# Generic_Robot_Controller_ver1.net
KiCad netlist of a schematic drawn in EasyEDA Pro
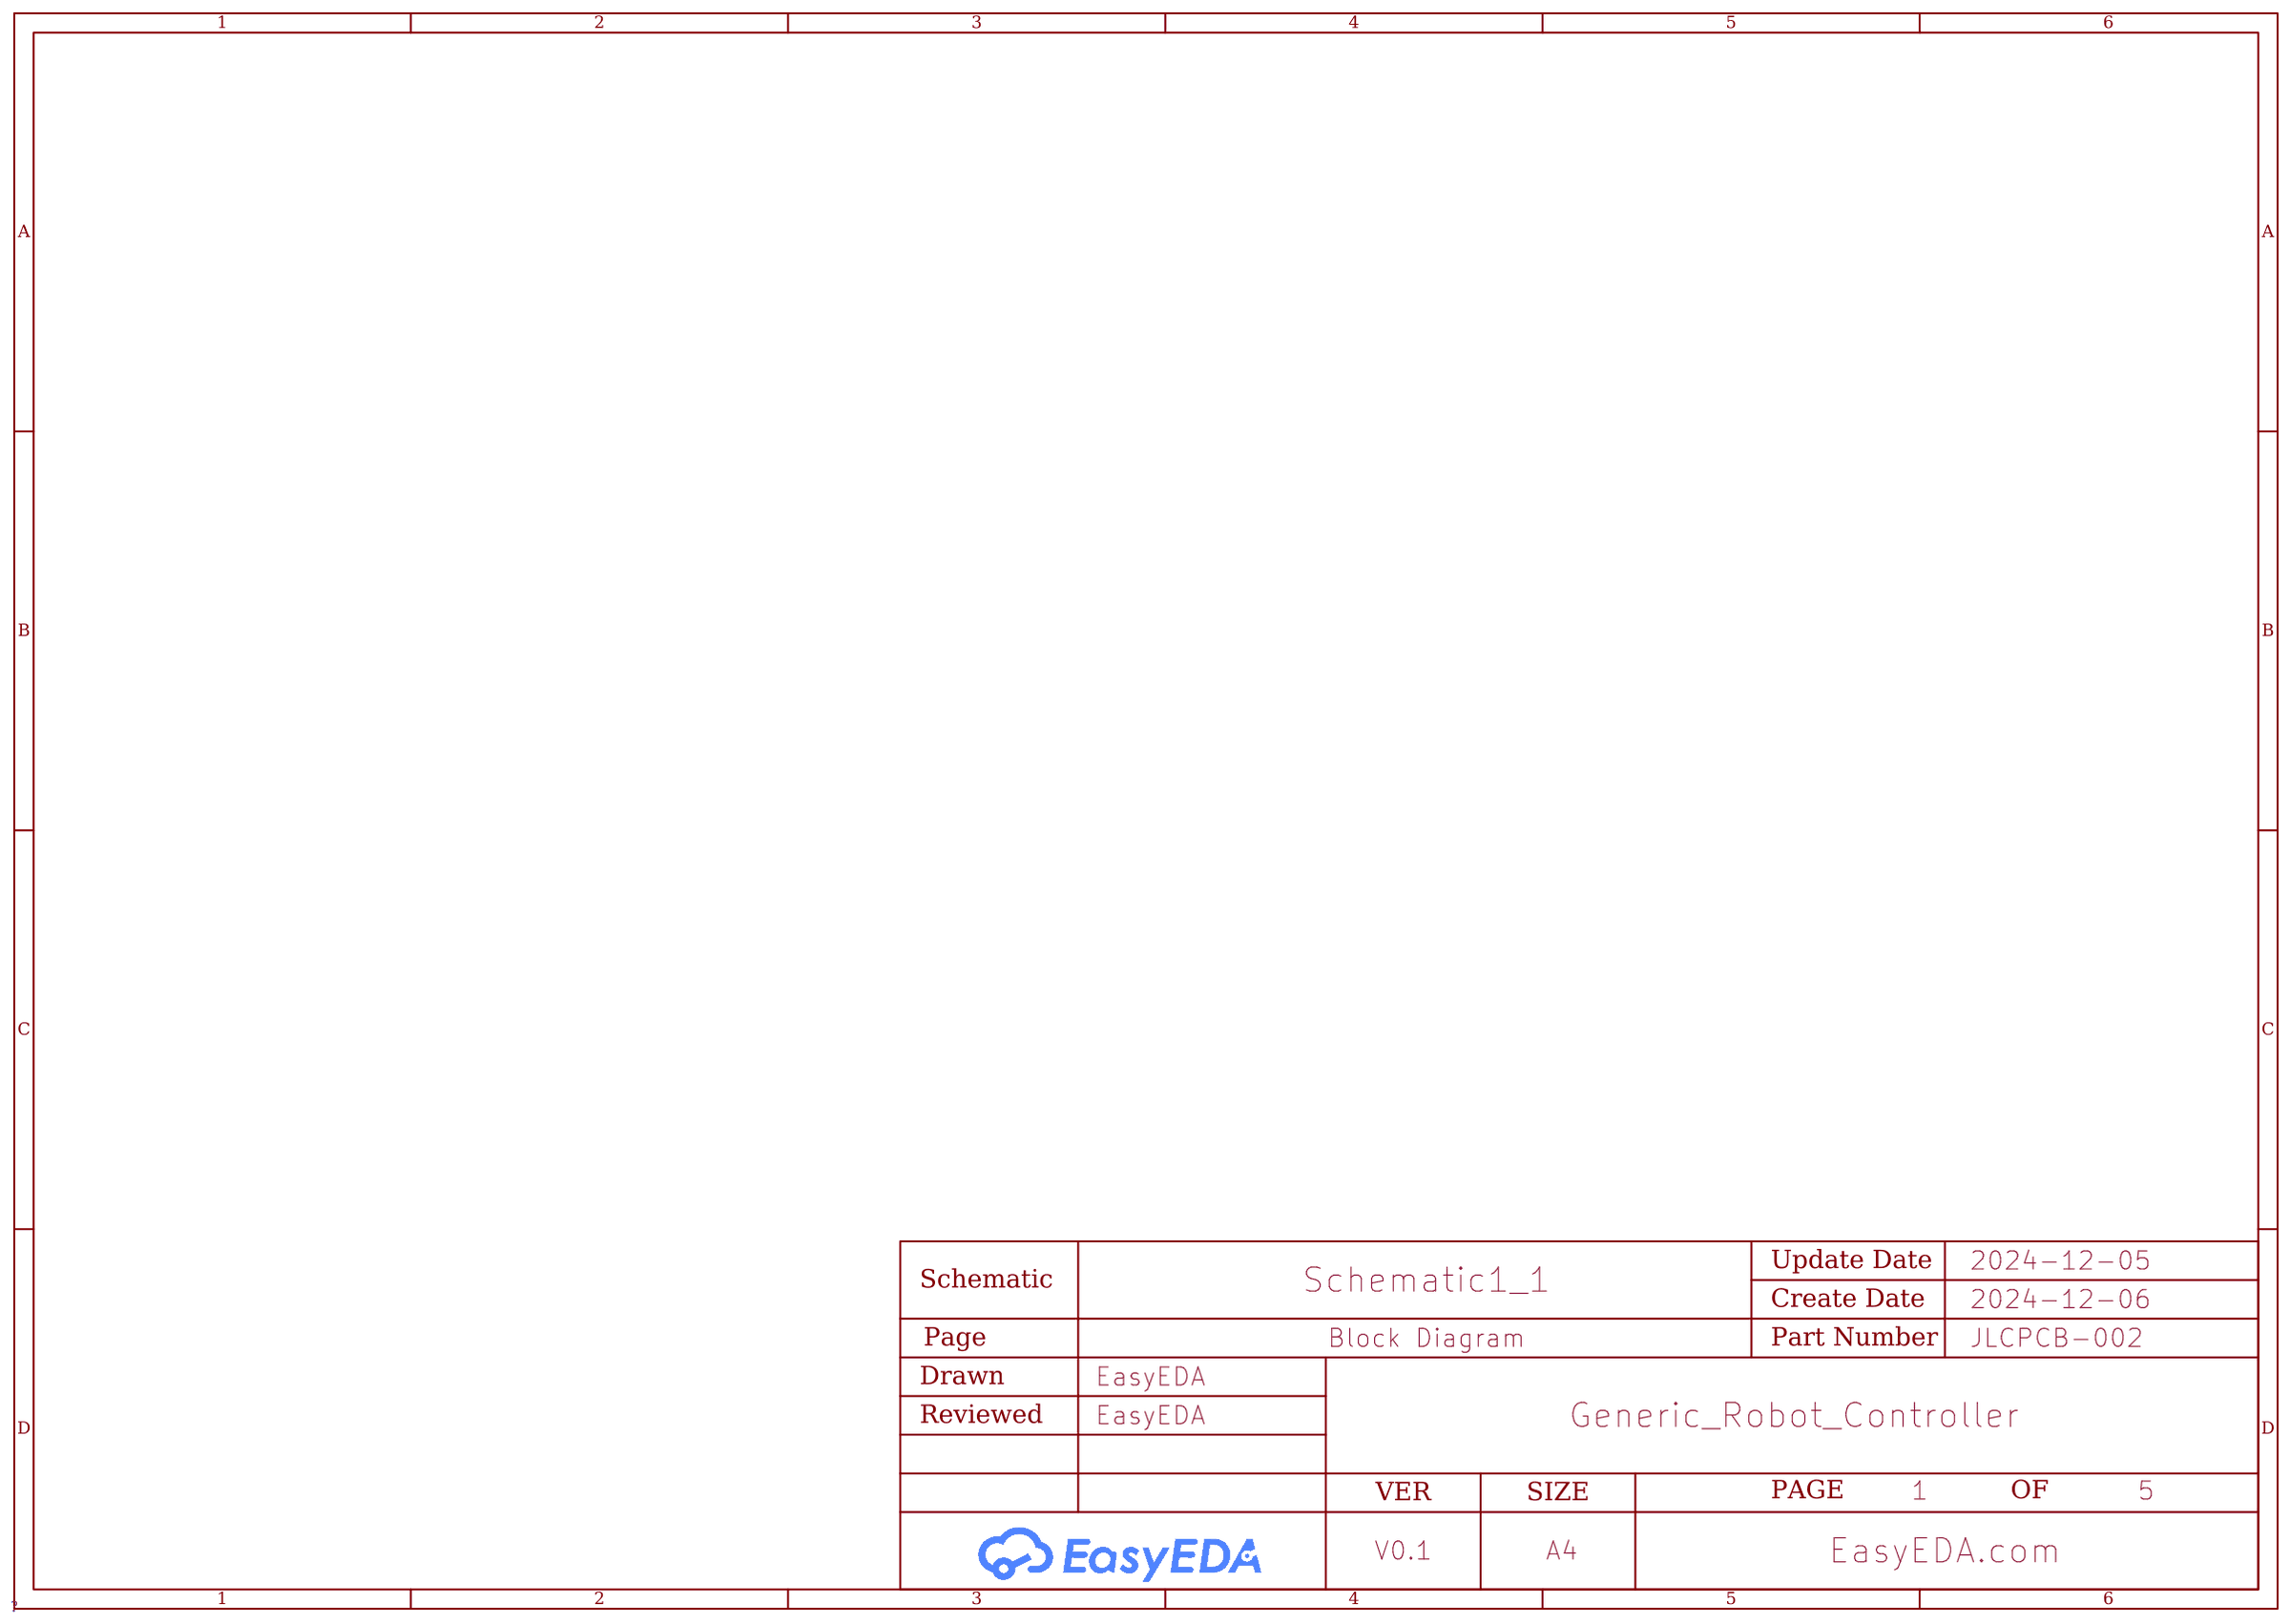
[diagram p0: Block Diagram]
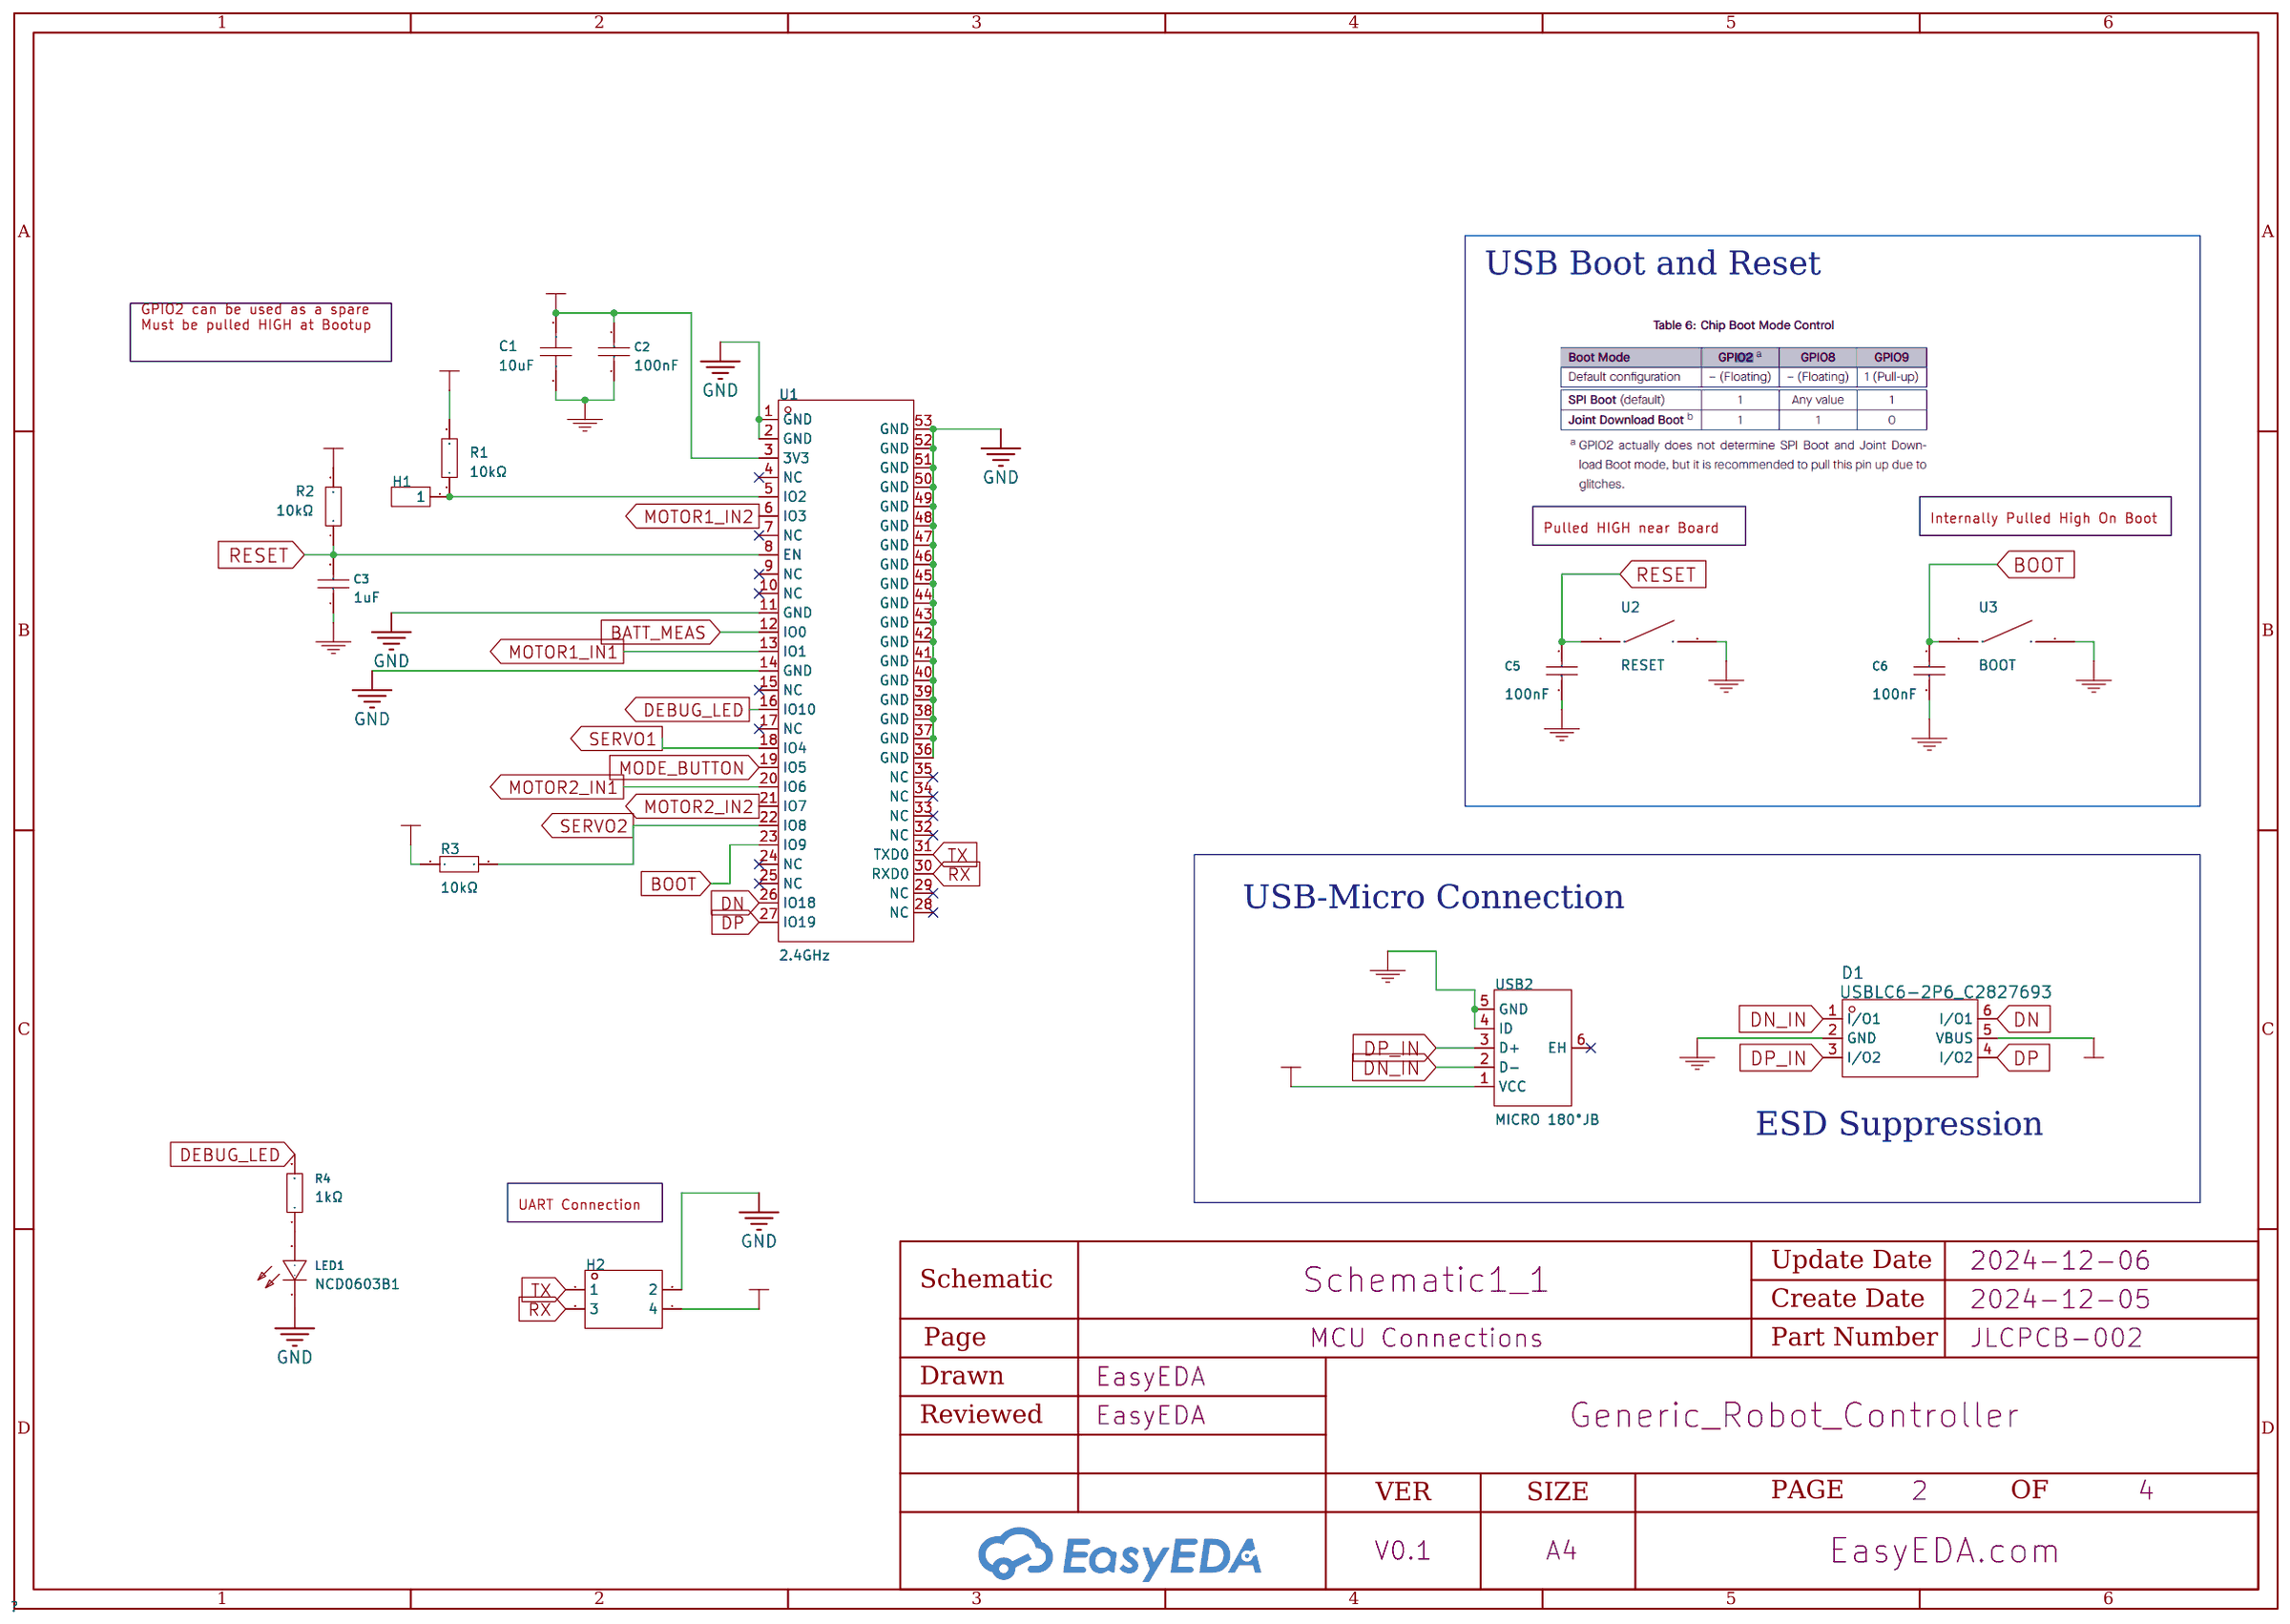
[diagram p1: MCU Connections]
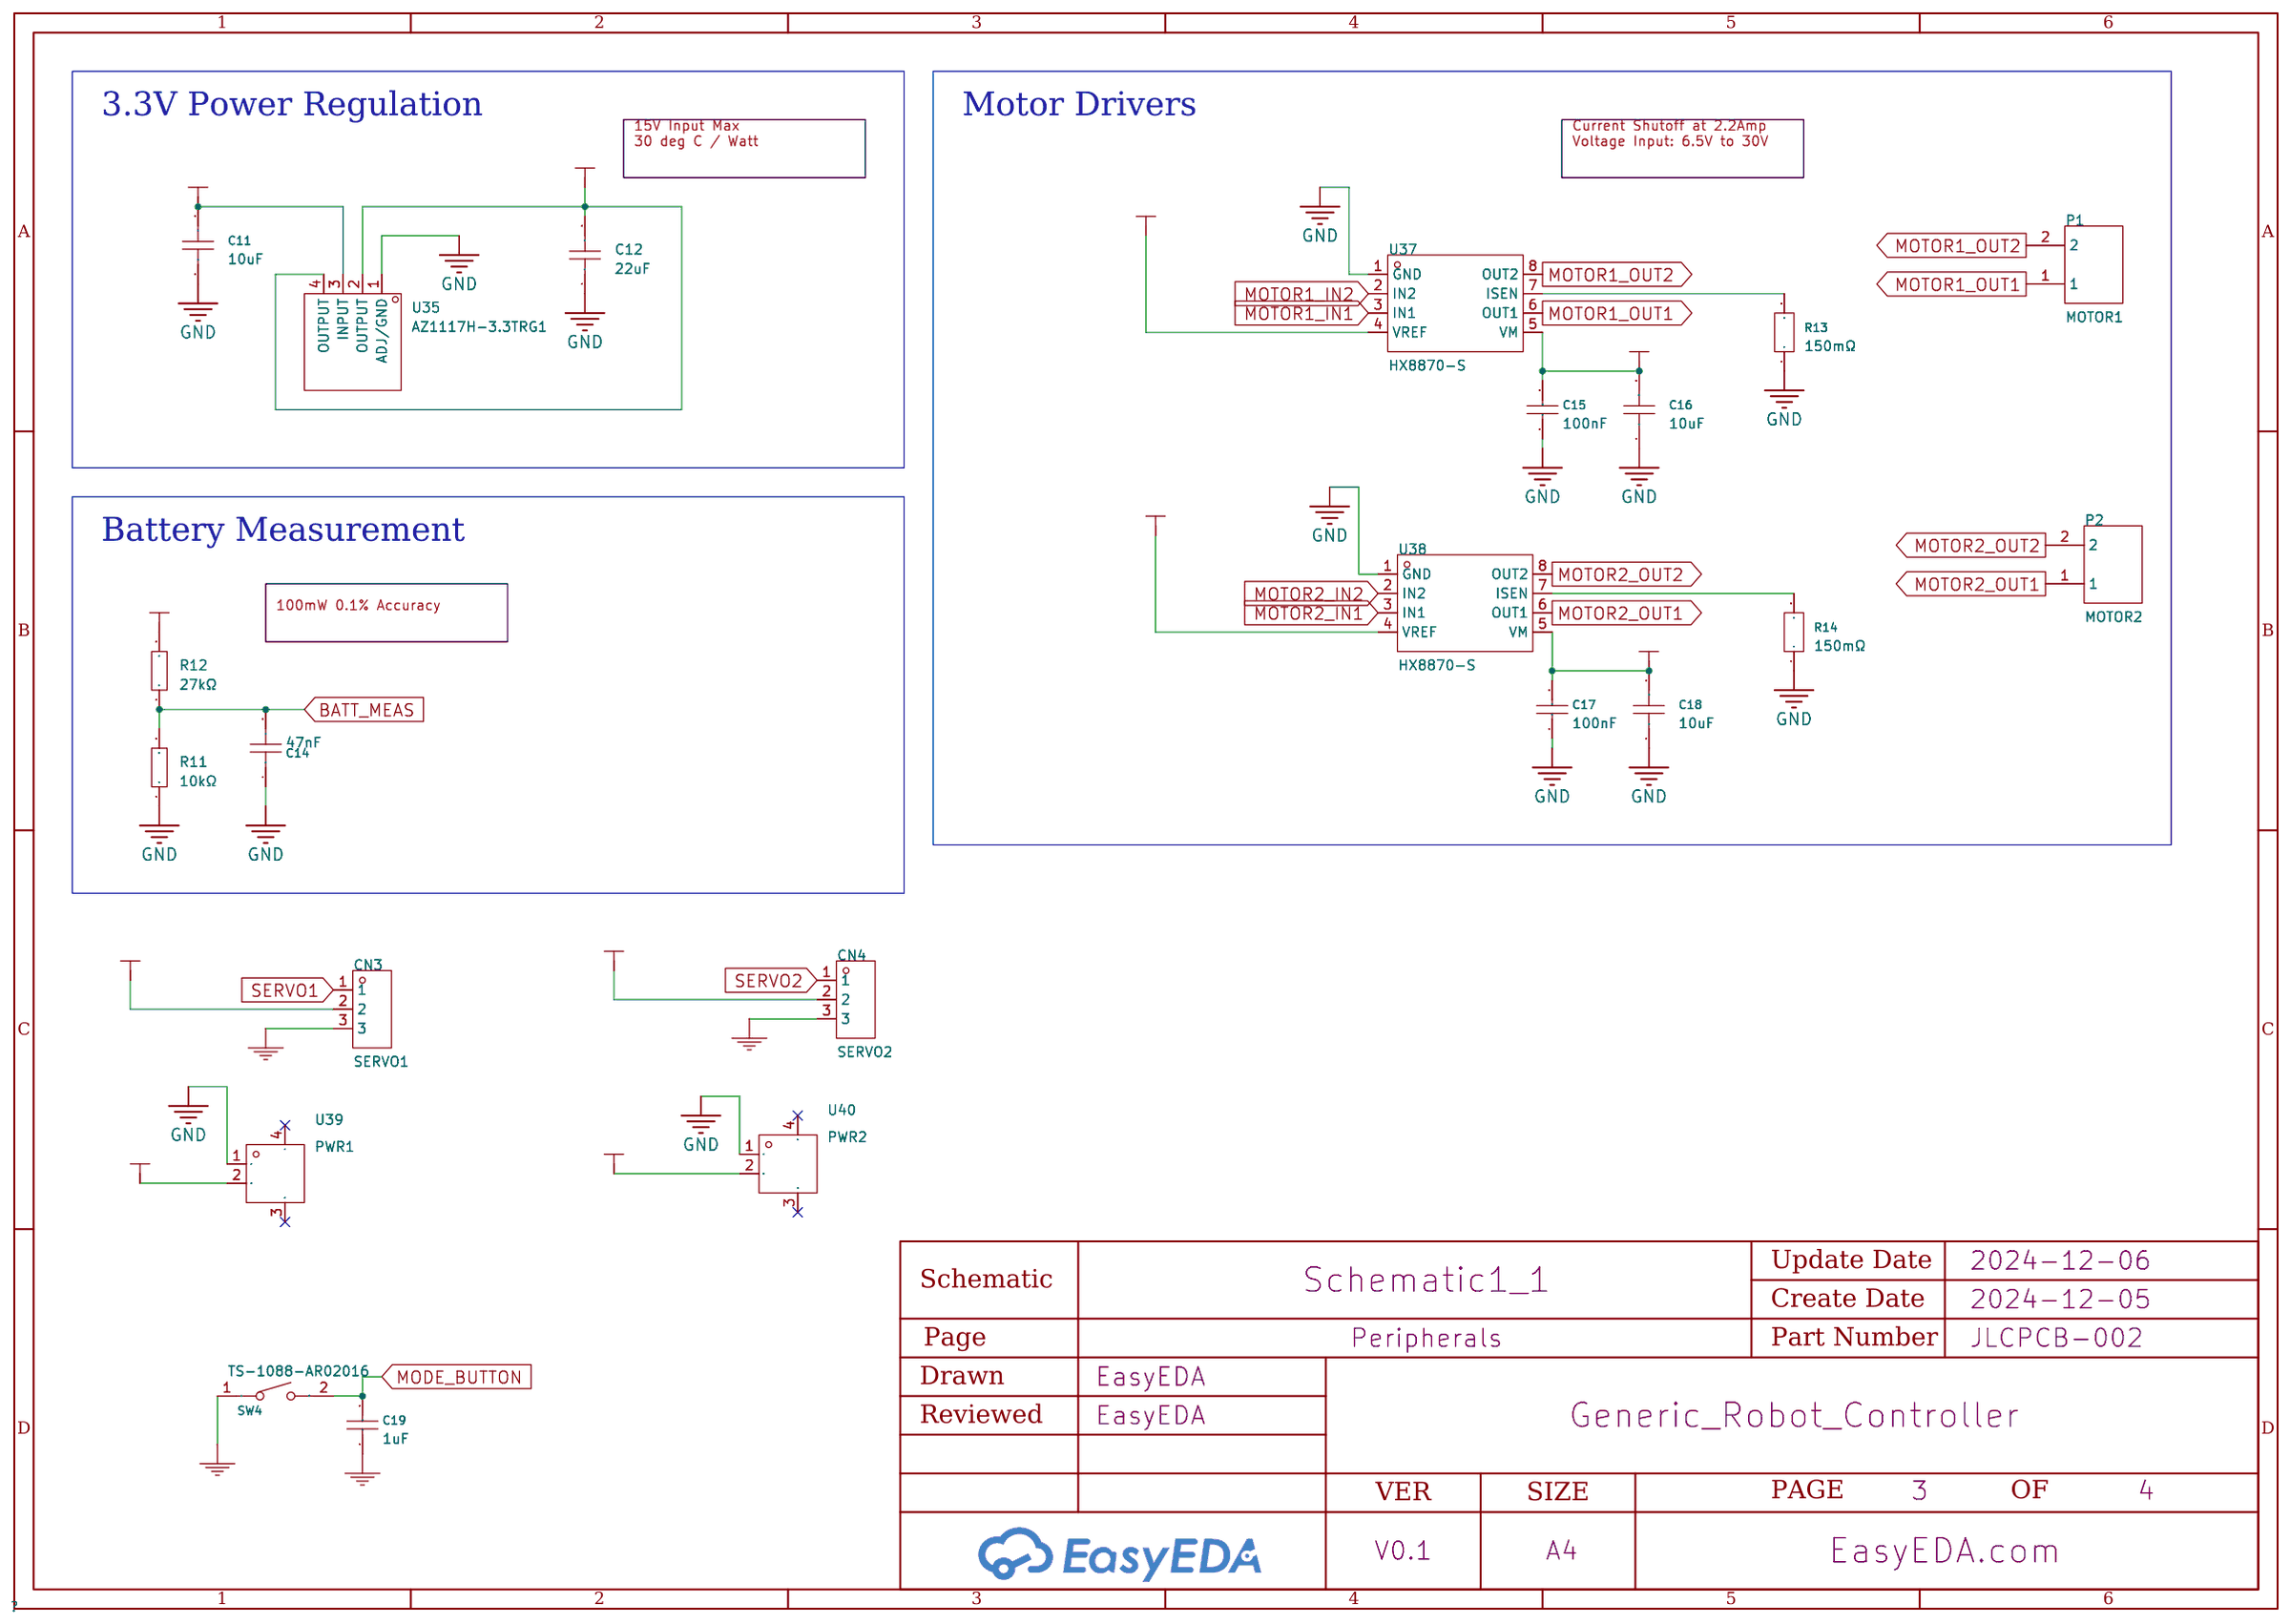
[diagram p2: Peripherals]
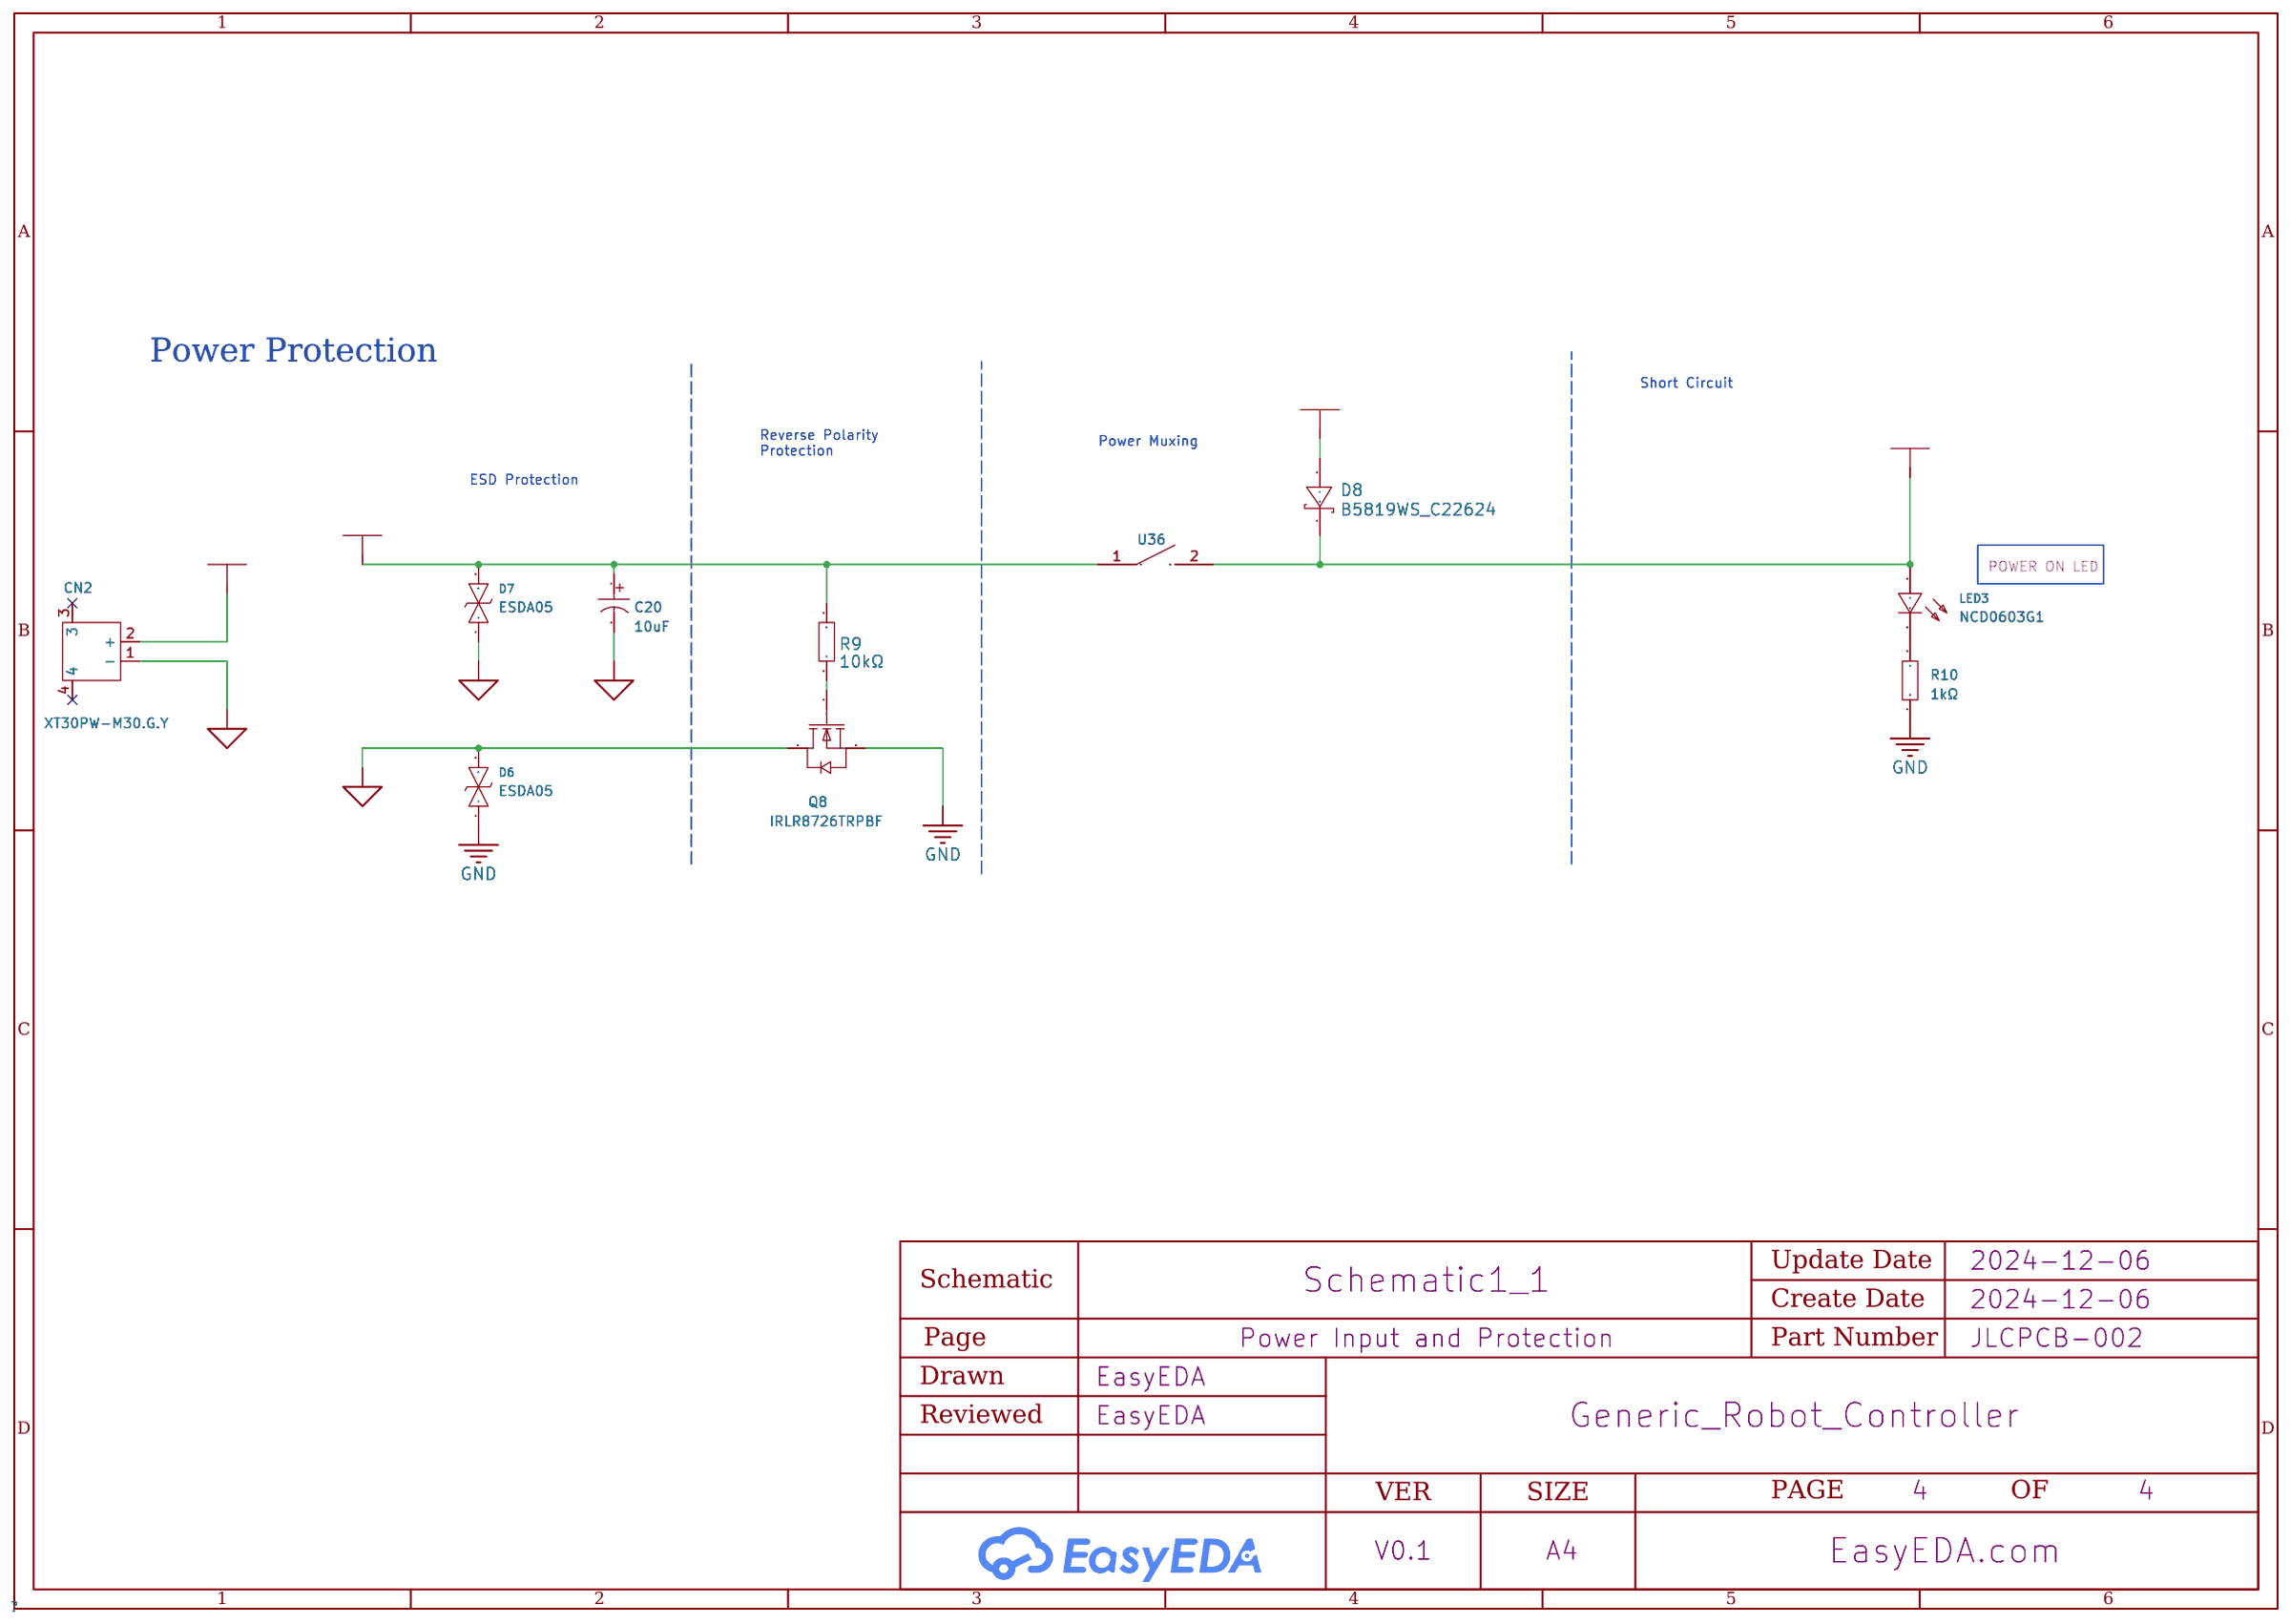
[diagram p3: Power Input and Protection]

(export (version "E")
  (design (tool "Eeschema 10.0.6"))
  (components
    (comp (ref "C1")
      (value "10uF")
      (footprint "easyedapro:C0402")
      (fields
        (field (name "Manufacturer Part") "CL05A106MP5NUNC")
        (field (name "Manufacturer") "SAMSUNG(三星)")
      )
      (libsource (lib "easyedapro") (part "CL05A106MP5NUNC_C315248"))
    )
    (comp (ref "C2")
      (value "100nF")
      (footprint "easyedapro:C0402")
      (fields
        (field (name "Manufacturer Part") "CL05B104KO5NNNC")
        (field (name "Manufacturer") "SAMSUNG(三星)")
      )
      (libsource (lib "easyedapro") (part "CL05B104KO5NNNC"))
    )
    (comp (ref "C3")
      (value "1uF")
      (footprint "easyedapro:C0402")
      (fields
        (field (name "Manufacturer Part") "CL05A105KO5NNNC")
        (field (name "Manufacturer") "SAMSUNG(三星)")
      )
      (libsource (lib "easyedapro") (part "CL05A105KO5NNNC"))
    )
    (comp (ref "C5")
      (value "100nF")
      (footprint "easyedapro:C0402")
      (fields
        (field (name "Manufacturer Part") "CL05B104KO5NNNC")
        (field (name "Manufacturer") "SAMSUNG(三星)")
      )
      (libsource (lib "easyedapro") (part "CL05B104KO5NNNC"))
    )
    (comp (ref "C6")
      (value "100nF")
      (footprint "easyedapro:C0402")
      (fields
        (field (name "Manufacturer Part") "CL05B104KO5NNNC")
        (field (name "Manufacturer") "SAMSUNG(三星)")
      )
      (libsource (lib "easyedapro") (part "CL05B104KO5NNNC"))
    )
    (comp (ref "D1")
      (value "USBLC6-2P6_C2827693")
      (footprint "easyedapro:SOT-666-6_L1.6-W1.2-P0.50-LS1.6-BL")
      (fields (field (name "Manufacturer Part") "USBLC6-2P6") (field (name "Manufacturer") "TECH PUBLIC(台舟)"))
      (libsource (lib "easyedapro") (part "USBLC6-2P6_C2827693"))
    )
    (comp (ref "H1")
      (value "~")
      (footprint "easyedapro:HDR-TH_1P-V-M_XKB_X4611WV-01I-C28D40")
      (libsource (lib "easyedapro") (part "HDR_1x1"))
    )
    (comp (ref "H2")
      (value "~")
      (footprint "easyedapro:HDR-TH_4P-P2.54-V-F-R2-C2-S2.54")
      (libsource (lib "easyedapro") (part "HDR-F-2.54_2x2"))
    )
    (comp (ref "LED1")
      (value "NCD0603B1")
      (footprint "easyedapro:LED0603-RD")
      (description "Emitted Color:blue")
      (fields (field (name "Manufacturer") "国星光电"))
      (libsource (lib "easyedapro") (part "FC-DA1608BK-470H10"))
    )
    (comp (ref "R1")
      (value "10kΩ")
      (footprint "easyedapro:R0402")
      (fields (field (name "Manufacturer Part") "RC0402FR-0710KL") (field (name "Manufacturer") "YAGEO(国巨)"))
      (libsource (lib "easyedapro") (part "RC0402FR-0710KL"))
    )
    (comp (ref "R2")
      (value "10kΩ")
      (footprint "easyedapro:R0402")
      (fields (field (name "Manufacturer Part") "RC0402FR-0710KL") (field (name "Manufacturer") "YAGEO(国巨)"))
      (libsource (lib "easyedapro") (part "RC0402FR-0710KL"))
    )
    (comp (ref "R3")
      (value "10kΩ")
      (footprint "easyedapro:R0402")
      (fields (field (name "Manufacturer Part") "RC0402FR-0710KL") (field (name "Manufacturer") "YAGEO(国巨)"))
      (libsource (lib "easyedapro") (part "RC0402FR-0710KL"))
    )
    (comp (ref "R4")
      (value "1kΩ")
      (footprint "easyedapro:R0402")
      (fields
        (field (name "Manufacturer Part") "0402WGF1001TCE")
        (field (name "Manufacturer") "UNI-ROYAL(厚声)")
      )
      (libsource (lib "easyedapro") (part "0402WGF1001TCE"))
    )
    (comp (ref "U1")
      (value "2.4GHz")
      (footprint "easyedapro:WIFIM-SMD_ESP32-C3-MINI-1")
      (fields
        (field (name "Manufacturer Part") "ESP32-C3-MINI-1-H4")
        (field (name "Manufacturer") "ESPRESSIF(乐鑫)")
      )
      (libsource (lib "easyedapro") (part "ESP32-C3-MINI-1-H4(4MB)"))
    )
    (comp (ref "U2")
      (value "RESET")
      (footprint "easyedapro:SW-SMD_4P-L3.0-W2.0-P0.85-LS3.5")
      (fields
        (field (name "Manufacturer Part") "TS2306A 240gf MSM 9")
        (field (name "Manufacturer") "SHOU HAN(首韩)")
      )
      (libsource (lib "easyedapro") (part "TS2306A 240GF MSM 9_C2976675"))
    )
    (comp (ref "U3")
      (value "BOOT")
      (footprint "easyedapro:SW-SMD_4P-L3.0-W2.0-P0.85-LS3.5")
      (fields
        (field (name "Manufacturer Part") "TS2306A 240gf MSM 9")
        (field (name "Manufacturer") "SHOU HAN(首韩)")
      )
      (libsource (lib "easyedapro") (part "TS2306A 240GF MSM 9_C2976675"))
    )
    (comp (ref "USB2")
      (value "MICRO 180°JB")
      (footprint "easyedapro:MINI-USB-SMD_U255-051N-4BH70-XS")
      (fields (field (name "Manufacturer") "SHOU HAN(首韩)"))
      (libsource (lib "easyedapro") (part "MICRO 180°JB"))
    )
    (comp (ref "C11")
      (value "10uF")
      (footprint "easyedapro:C0603")
      (fields
        (field (name "Manufacturer Part") "CL10A106MA8NRNC")
        (field (name "Manufacturer") "SAMSUNG(三星)")
      )
      (libsource (lib "easyedapro") (part "CL10A106MA8NRNC"))
    )
    (comp (ref "C12")
      (value "22uF")
      (footprint "easyedapro:C0402")
      (fields
        (field (name "Manufacturer Part") "GRM158R61A226ME15D")
        (field (name "Manufacturer") "muRata(村田)")
      )
      (libsource (lib "easyedapro") (part "GRM158R61A226ME15D"))
    )
    (comp (ref "C14")
      (value "47nF")
      (footprint "easyedapro:C0402")
      (fields
        (field (name "Manufacturer Part") "CC0402KRX7R9BB473")
        (field (name "Manufacturer") "YAGEO(国巨)")
      )
      (libsource (lib "easyedapro") (part "CC0402KRX7R9BB473"))
    )
    (comp (ref "C15")
      (value "100nF")
      (footprint "easyedapro:C0402")
      (fields
        (field (name "Manufacturer Part") "CL05B104KO5NNNC")
        (field (name "Manufacturer") "SAMSUNG(三星)")
      )
      (libsource (lib "easyedapro") (part "CL05B104KO5NNNC"))
    )
    (comp (ref "C16")
      (value "10uF")
      (footprint "easyedapro:C0603")
      (fields
        (field (name "Manufacturer Part") "CL10A106MA8NRNC")
        (field (name "Manufacturer") "SAMSUNG(三星)")
      )
      (libsource (lib "easyedapro") (part "CL10A106MA8NRNC"))
    )
    (comp (ref "C17")
      (value "100nF")
      (footprint "easyedapro:C0402")
      (fields
        (field (name "Manufacturer Part") "CL05B104KO5NNNC")
        (field (name "Manufacturer") "SAMSUNG(三星)")
      )
      (libsource (lib "easyedapro") (part "CL05B104KO5NNNC"))
    )
    (comp (ref "C18")
      (value "10uF")
      (footprint "easyedapro:C0603")
      (fields
        (field (name "Manufacturer Part") "CL10A106MA8NRNC")
        (field (name "Manufacturer") "SAMSUNG(三星)")
      )
      (libsource (lib "easyedapro") (part "CL10A106MA8NRNC"))
    )
    (comp (ref "C19")
      (value "1uF")
      (footprint "easyedapro:C0402")
      (fields
        (field (name "Manufacturer Part") "CL05A105KO5NNNC")
        (field (name "Manufacturer") "SAMSUNG(三星)")
      )
      (libsource (lib "easyedapro") (part "CL05A105KO5NNNC"))
    )
    (comp (ref "CN3")
      (value "SERVO1")
      (footprint "easyedapro:CONN-TH_3P-P2.00_PH-3AK")
      (fields (field (name "Manufacturer Part") "HC-PH-3A-B-K-10") (field (name "Manufacturer") "HCTL(华灿天禄)"))
      (libsource (lib "easyedapro") (part "HC-PH-3A-B-K-10"))
    )
    (comp (ref "CN4")
      (value "SERVO2")
      (footprint "easyedapro:CONN-TH_3P-P2.00_PH-3AK")
      (fields (field (name "Manufacturer Part") "HC-PH-3A-B-K-10") (field (name "Manufacturer") "HCTL(华灿天禄)"))
      (libsource (lib "easyedapro") (part "HC-PH-3A-B-K-10"))
    )
    (comp (ref "P1")
      (value "MOTOR1")
      (footprint "easyedapro:CONN-TH_2P-P2.00_PH-2A_C2319")
      (fields (field (name "Manufacturer Part") "PH-2A") (field (name "Manufacturer") "BOOMELE(博穆精密)"))
      (libsource (lib "easyedapro") (part "PH-2A_C2319"))
    )
    (comp (ref "P2")
      (value "MOTOR2")
      (footprint "easyedapro:CONN-TH_2P-P2.00_PH-2A_C2319")
      (fields (field (name "Manufacturer Part") "PH-2A") (field (name "Manufacturer") "BOOMELE(博穆精密)"))
      (libsource (lib "easyedapro") (part "PH-2A_C2319"))
    )
    (comp (ref "R11")
      (value "10kΩ")
      (footprint "easyedapro:R0603")
      (fields (field (name "Manufacturer Part") "RT0603BRD0710KL") (field (name "Manufacturer") "YAGEO(国巨)"))
      (libsource (lib "easyedapro") (part "RT0603BRD0710KL"))
    )
    (comp (ref "R12")
      (value "27kΩ")
      (footprint "easyedapro:R0603")
      (fields (field (name "Manufacturer Part") "RT0603BRD0727KL") (field (name "Manufacturer") "YAGEO(国巨)"))
      (libsource (lib "easyedapro") (part "RT0603BRD0727KL"))
    )
    (comp (ref "R13")
      (value "150mΩ")
      (footprint "easyedapro:RES-SMD_L6.4-W3.2-1")
      (fields
        (field (name "Manufacturer Part") "HoJLR2512-3W-150mR-1%")
        (field (name "Manufacturer") "Milliohm(毫欧)")
      )
      (libsource (lib "easyedapro") (part "HOJLR2512-3W-150MR-1%"))
    )
    (comp (ref "R14")
      (value "150mΩ")
      (footprint "easyedapro:RES-SMD_L6.4-W3.2-1")
      (fields
        (field (name "Manufacturer Part") "HoJLR2512-3W-150mR-1%")
        (field (name "Manufacturer") "Milliohm(毫欧)")
      )
      (libsource (lib "easyedapro") (part "HOJLR2512-3W-150MR-1%"))
    )
    (comp (ref "SW4")
      (value "TS-1088-AR02016")
      (footprint "easyedapro:SW-SMD_L3.9-W3.0-P4.45")
      (fields (field (name "Manufacturer") "XUNPU(讯普)"))
      (libsource (lib "easyedapro") (part "TS-1088-AR02016"))
    )
    (comp (ref "U35")
      (value "AZ1117H-3.3TRG1")
      (footprint "easyedapro:SOT-223-3_L6.5-W3.4-P2.30-LS7.0-BR")
      (fields (field (name "Manufacturer") "DIODES(美台)"))
      (libsource (lib "easyedapro") (part "AZ1117H-3.3TRG1"))
    )
    (comp (ref "U37")
      (value "HX8870-S")
      (footprint "easyedapro:SOIC-8_L4.9-W3.9-P1.27-LS6.0-BL")
      (fields (field (name "Manufacturer") "ZHHXDZ(海芯电子)"))
      (libsource (lib "easyedapro") (part "HX8870-S"))
    )
    (comp (ref "U38")
      (value "HX8870-S")
      (footprint "easyedapro:SOIC-8_L4.9-W3.9-P1.27-LS6.0-BL")
      (fields (field (name "Manufacturer") "ZHHXDZ(海芯电子)"))
      (libsource (lib "easyedapro") (part "HX8870-S"))
    )
    (comp (ref "U39")
      (value "PWR1")
      (footprint "easyedapro:CONN-TH_XT30PW-F-1")
      (fields (field (name "Manufacturer Part") "XT30PW-F20.G.Y") (field (name "Manufacturer") "AMASS(艾迈斯)"))
      (libsource (lib "easyedapro") (part "XT30PW-F"))
    )
    (comp (ref "U40")
      (value "PWR2")
      (footprint "easyedapro:CONN-TH_XT30PW-F-1")
      (fields (field (name "Manufacturer Part") "XT30PW-F20.G.Y") (field (name "Manufacturer") "AMASS(艾迈斯)"))
      (libsource (lib "easyedapro") (part "XT30PW-F"))
    )
    (comp (ref "C20")
      (value "10uF")
      (footprint "easyedapro:CAP-SMD_BD4.0-L4.3-W4.3-FD")
      (fields (field (name "Manufacturer Part") "RVT1V100M0405") (field (name "Manufacturer") "ROQANG(容强)"))
      (libsource (lib "easyedapro") (part "RVT1V100M0405-C72485"))
    )
    (comp (ref "CN2")
      (value "XT30PW-M30.G.Y")
      (footprint "easyedapro:CONN-TH_XT30PW-M")
      (fields (field (name "Manufacturer") "AMASS(艾迈斯)"))
      (libsource (lib "easyedapro") (part "XT30PW-M"))
    )
    (comp (ref "D6")
      (value "ESDA05")
      (footprint "easyedapro:D0603-BI")
      (fields (field (name "Manufacturer") "Leiditech(雷卯电子)"))
      (libsource (lib "easyedapro") (part "ESDA05"))
    )
    (comp (ref "D7")
      (value "ESDA05")
      (footprint "easyedapro:D0603-BI")
      (fields (field (name "Manufacturer") "Leiditech(雷卯电子)"))
      (libsource (lib "easyedapro") (part "ESDA05"))
    )
    (comp (ref "D8")
      (value "B5819WS_C22624")
      (footprint "easyedapro:SOD-323_L1.8-W1.3-LS2.5-RD")
      (fields (field (name "Manufacturer Part") "B5819WS") (field (name "Manufacturer") "CJ(江苏长电/长晶)"))
      (libsource (lib "easyedapro") (part "B5819WS_C22624"))
    )
    (comp (ref "LED3")
      (value "NCD0603G1")
      (footprint "easyedapro:LED0603-RD")
      (description "Emitted Color:Emerald")
      (fields (field (name "Manufacturer") "国星光电"))
      (libsource (lib "easyedapro") (part "FC-D1608UGK-520D10"))
    )
    (comp (ref "Q8")
      (value "IRLR8726TRPBF")
      (footprint "easyedapro:TO-252-2_L6.6-W6.1-P4.58-LS9.9-TL")
      (fields (field (name "Manufacturer") "Infineon(英飞凌)"))
      (libsource (lib "easyedapro") (part "IRLR8726TRPBF"))
    )
    (comp (ref "R9")
      (value "10kΩ")
      (footprint "easyedapro:R0603")
      (fields (field (name "Manufacturer Part") "RC0603FR-0710KL") (field (name "Manufacturer") "YAGEO(国巨)"))
      (libsource (lib "easyedapro") (part "10kΩ"))
    )
    (comp (ref "R10")
      (value "1kΩ")
      (footprint "easyedapro:R0603")
      (fields
        (field (name "Manufacturer Part") "0603WAF1001T5E")
        (field (name "Manufacturer") "UNI-ROYAL(厚声)")
      )
      (libsource (lib "easyedapro") (part "0603WAF1001T5E"))
    )
    (comp (ref "U36")
      (value "~")
      (footprint "easyedapro:screw_switch")
      (libsource (lib "easyedapro") (part "screw_switch"))
    )
  )
  (nets
    (net (code "1") (name "3V3") (class "Default")
      (node (ref "C1") (pin "2") (pinfunction "2_2") (pintype "unspecified"))
      (node (ref "C12") (pin "2") (pinfunction "2_2") (pintype "unspecified"))
      (node (ref "C2") (pin "2") (pinfunction "2_2") (pintype "input"))
      (node (ref "CN3") (pin "2") (pinfunction "2_2") (pintype "unspecified"))
      (node (ref "CN4") (pin "2") (pinfunction "2_2") (pintype "unspecified"))
      (node (ref "R1") (pin "2") (pinfunction "2_2") (pintype "input"))
      (node (ref "R2") (pin "2") (pinfunction "2_2") (pintype "input"))
      (node (ref "R3") (pin "1") (pinfunction "1_1") (pintype "input"))
      (node (ref "U1") (pin "3") (pinfunction "3V3_3") (pintype "unspecified"))
      (node (ref "U35") (pin "2") (pinfunction "OUTPUT_2") (pintype "unspecified"))
      (node (ref "U35") (pin "4") (pinfunction "OUTPUT_4") (pintype "unspecified"))
      (node (ref "U37") (pin "4") (pinfunction "VREF_4") (pintype "unspecified"))
      (node (ref "U38") (pin "4") (pinfunction "VREF_4") (pintype "unspecified"))
    )
    (net (code "2") (name "BATT_GND") (class "Default")
      (node (ref "C20") (pin "2") (pinfunction "2_2") (pintype "input"))
      (node (ref "CN2") (pin "1") (pinfunction "-_1") (pintype "unspecified"))
      (node (ref "D6") (pin "2") (pinfunction "2_2") (pintype "input"))
      (node (ref "D7") (pin "1") (pinfunction "1_1") (pintype "input"))
      (node (ref "Q8") (pin "2") (pinfunction "D_2") (pintype "unspecified"))
    )
    (net (code "3") (name "BATT_IN") (class "Default")
      (node (ref "C20") (pin "1") (pinfunction "1_1") (pintype "input"))
      (node (ref "CN2") (pin "2") (pinfunction "+_2") (pintype "unspecified"))
      (node (ref "D7") (pin "2") (pinfunction "2_2") (pintype "input"))
      (node (ref "R9") (pin "1") (pinfunction "1_1") (pintype "input"))
      (node (ref "U36") (pin "1") (pinfunction "1_1") (pintype "input"))
    )
    (net (code "4") (name "BATT_MEAS") (class "Default")
      (node (ref "C14") (pin "2") (pinfunction "2_2") (pintype "input"))
      (node (ref "R11") (pin "2") (pinfunction "2_2") (pintype "input"))
      (node (ref "R12") (pin "1") (pinfunction "1_1") (pintype "unspecified"))
      (node (ref "U1") (pin "12") (pinfunction "IO0_12") (pintype "unspecified"))
    )
    (net (code "5") (name "BOOT") (class "Default")
      (node (ref "C6") (pin "2") (pinfunction "2_2") (pintype "input"))
      (node (ref "U1") (pin "23") (pinfunction "IO9_23") (pintype "unspecified"))
      (node (ref "U3") (pin "1") (pinfunction "1_1") (pintype "input"))
    )
    (net (code "6") (name "DEBUG_LED") (class "Default")
      (node (ref "R4") (pin "2") (pinfunction "2_2") (pintype "input"))
      (node (ref "U1") (pin "16") (pinfunction "IO10_16") (pintype "unspecified"))
    )
    (net (code "7") (name "DN") (class "Default")
      (node (ref "D1") (pin "6") (pinfunction "I/O1_6") (pintype "input"))
      (node (ref "U1") (pin "26") (pinfunction "IO18_26") (pintype "unspecified"))
    )
    (net (code "8") (name "DN_IN") (class "Default")
      (node (ref "D1") (pin "1") (pinfunction "I/O1_1") (pintype "input"))
      (node (ref "USB2") (pin "2") (pinfunction "D-_2") (pintype "input"))
    )
    (net (code "9") (name "DP") (class "Default")
      (node (ref "D1") (pin "4") (pinfunction "I/O2_4") (pintype "input"))
      (node (ref "U1") (pin "27") (pinfunction "IO19_27") (pintype "unspecified"))
    )
    (net (code "10") (name "DP_IN") (class "Default")
      (node (ref "D1") (pin "3") (pinfunction "I/O2_3") (pintype "input"))
      (node (ref "USB2") (pin "3") (pinfunction "D+_3") (pintype "input"))
    )
    (net (code "11") (name "GND") (class "Default")
      (node (ref "C1") (pin "1") (pinfunction "1_1") (pintype "unspecified"))
      (node (ref "C11") (pin "1") (pinfunction "1_1") (pintype "input"))
      (node (ref "C12") (pin "1") (pinfunction "1_1") (pintype "unspecified"))
      (node (ref "C14") (pin "1") (pinfunction "1_1") (pintype "input"))
      (node (ref "C15") (pin "1") (pinfunction "1_1") (pintype "input"))
      (node (ref "C16") (pin "1") (pinfunction "1_1") (pintype "input"))
      (node (ref "C17") (pin "1") (pinfunction "1_1") (pintype "input"))
      (node (ref "C18") (pin "1") (pinfunction "1_1") (pintype "input"))
      (node (ref "C19") (pin "1") (pinfunction "1_1") (pintype "input"))
      (node (ref "C2") (pin "1") (pinfunction "1_1") (pintype "input"))
      (node (ref "C3") (pin "1") (pinfunction "1_1") (pintype "input"))
      (node (ref "C5") (pin "1") (pinfunction "1_1") (pintype "input"))
      (node (ref "C6") (pin "1") (pinfunction "1_1") (pintype "input"))
      (node (ref "CN3") (pin "3") (pinfunction "3_3") (pintype "unspecified"))
      (node (ref "CN4") (pin "3") (pinfunction "3_3") (pintype "unspecified"))
      (node (ref "D1") (pin "2") (pinfunction "GND_2") (pintype "input"))
      (node (ref "D6") (pin "1") (pinfunction "1_1") (pintype "input"))
      (node (ref "H2") (pin "2") (pinfunction "2_2") (pintype "input"))
      (node (ref "LED1") (pin "1") (pinfunction "-_1") (pintype "input"))
      (node (ref "Q8") (pin "3") (pinfunction "S_3") (pintype "unspecified"))
      (node (ref "R10") (pin "1") (pinfunction "1_1") (pintype "input"))
      (node (ref "R11") (pin "1") (pinfunction "1_1") (pintype "input"))
      (node (ref "R13") (pin "1") (pinfunction "1_1") (pintype "input"))
      (node (ref "R14") (pin "1") (pinfunction "1_1") (pintype "input"))
      (node (ref "SW4") (pin "1") (pinfunction "1_1") (pintype "input"))
      (node (ref "U1") (pin "1") (pinfunction "GND_1") (pintype "unspecified"))
      (node (ref "U1") (pin "11") (pinfunction "GND_11") (pintype "unspecified"))
      (node (ref "U1") (pin "14") (pinfunction "GND_14") (pintype "unspecified"))
      (node (ref "U1") (pin "2") (pinfunction "GND_2") (pintype "unspecified"))
      (node (ref "U1") (pin "36") (pinfunction "GND_36") (pintype "unspecified"))
      (node (ref "U1") (pin "37") (pinfunction "GND_37") (pintype "unspecified"))
      (node (ref "U1") (pin "38") (pinfunction "GND_38") (pintype "unspecified"))
      (node (ref "U1") (pin "39") (pinfunction "GND_39") (pintype "unspecified"))
      (node (ref "U1") (pin "40") (pinfunction "GND_40") (pintype "unspecified"))
      (node (ref "U1") (pin "41") (pinfunction "GND_41") (pintype "unspecified"))
      (node (ref "U1") (pin "42") (pinfunction "GND_42") (pintype "unspecified"))
      (node (ref "U1") (pin "43") (pinfunction "GND_43") (pintype "unspecified"))
      (node (ref "U1") (pin "44") (pinfunction "GND_44") (pintype "unspecified"))
      (node (ref "U1") (pin "45") (pinfunction "GND_45") (pintype "unspecified"))
      (node (ref "U1") (pin "46") (pinfunction "GND_46") (pintype "unspecified"))
      (node (ref "U1") (pin "47") (pinfunction "GND_47") (pintype "unspecified"))
      (node (ref "U1") (pin "48") (pinfunction "GND_48") (pintype "unspecified"))
      (node (ref "U1") (pin "49") (pinfunction "GND_49") (pintype "unspecified"))
      (node (ref "U1") (pin "50") (pinfunction "GND_50") (pintype "unspecified"))
      (node (ref "U1") (pin "51") (pinfunction "GND_51") (pintype "unspecified"))
      (node (ref "U1") (pin "52") (pinfunction "GND_52") (pintype "unspecified"))
      (node (ref "U1") (pin "53") (pinfunction "GND_53") (pintype "unspecified"))
      (node (ref "U2") (pin "2") (pinfunction "2_2") (pintype "input"))
      (node (ref "U3") (pin "2") (pinfunction "2_2") (pintype "input"))
      (node (ref "U35") (pin "1") (pinfunction "ADJ/GND_1") (pintype "unspecified"))
      (node (ref "U37") (pin "1") (pinfunction "GND_1") (pintype "unspecified"))
      (node (ref "U38") (pin "1") (pinfunction "GND_1") (pintype "unspecified"))
      (node (ref "U39") (pin "1") (pinfunction "1_1") (pintype "unspecified"))
      (node (ref "U40") (pin "1") (pinfunction "1_1") (pintype "unspecified"))
      (node (ref "USB2") (pin "4") (pinfunction "ID_4") (pintype "input"))
      (node (ref "USB2") (pin "5") (pinfunction "GND_5") (pintype "input"))
    )
    (net (code "12") (name "MODE_BUTTON") (class "Default")
      (node (ref "C19") (pin "2") (pinfunction "2_2") (pintype "input"))
      (node (ref "SW4") (pin "2") (pinfunction "2_2") (pintype "input"))
      (node (ref "U1") (pin "19") (pinfunction "IO5_19") (pintype "unspecified"))
    )
    (net (code "13") (name "MOTOR1_IN1") (class "Default")
      (node (ref "U1") (pin "13") (pinfunction "IO1_13") (pintype "unspecified"))
      (node (ref "U37") (pin "3") (pinfunction "IN1_3") (pintype "unspecified"))
    )
    (net (code "14") (name "MOTOR1_IN2") (class "Default")
      (node (ref "U1") (pin "6") (pinfunction "IO3_6") (pintype "unspecified"))
      (node (ref "U37") (pin "2") (pinfunction "IN2_2") (pintype "unspecified"))
    )
    (net (code "15") (name "MOTOR1_OUT1") (class "Default")
      (node (ref "P1") (pin "1") (pinfunction "1_1") (pintype "input"))
      (node (ref "U37") (pin "6") (pinfunction "OUT1_6") (pintype "unspecified"))
    )
    (net (code "16") (name "MOTOR1_OUT2") (class "Default")
      (node (ref "P1") (pin "2") (pinfunction "2_2") (pintype "input"))
      (node (ref "U37") (pin "8") (pinfunction "OUT2_8") (pintype "unspecified"))
    )
    (net (code "17") (name "MOTOR2_IN1") (class "Default")
      (node (ref "U1") (pin "20") (pinfunction "IO6_20") (pintype "unspecified"))
      (node (ref "U38") (pin "3") (pinfunction "IN1_3") (pintype "unspecified"))
    )
    (net (code "18") (name "MOTOR2_IN2") (class "Default")
      (node (ref "U1") (pin "21") (pinfunction "IO7_21") (pintype "unspecified"))
      (node (ref "U38") (pin "2") (pinfunction "IN2_2") (pintype "unspecified"))
    )
    (net (code "19") (name "MOTOR2_OUT1") (class "Default")
      (node (ref "P2") (pin "1") (pinfunction "1_1") (pintype "input"))
      (node (ref "U38") (pin "6") (pinfunction "OUT1_6") (pintype "unspecified"))
    )
    (net (code "20") (name "MOTOR2_OUT2") (class "Default")
      (node (ref "P2") (pin "2") (pinfunction "2_2") (pintype "input"))
      (node (ref "U38") (pin "8") (pinfunction "OUT2_8") (pintype "unspecified"))
    )
    (net (code "21") (name "Net-(LED1-+)") (class "Default")
      (node (ref "LED1") (pin "2") (pinfunction "+_2") (pintype "input"))
      (node (ref "R4") (pin "1") (pinfunction "1_1") (pintype "input"))
    )
    (net (code "22") (name "Net-(LED3-K)") (class "Default")
      (node (ref "LED3") (pin "1") (pinfunction "K_1") (pintype "input"))
      (node (ref "R10") (pin "2") (pinfunction "2_2") (pintype "input"))
    )
    (net (code "23") (name "Net-(Q8-G)") (class "Default")
      (node (ref "Q8") (pin "1") (pinfunction "G_1") (pintype "unspecified"))
      (node (ref "R9") (pin "2") (pinfunction "2_2") (pintype "input"))
    )
    (net (code "24") (name "Net-(U1-IO2)") (class "Default")
      (node (ref "H1") (pin "1") (pinfunction "1_1") (pintype "unspecified"))
      (node (ref "R1") (pin "1") (pinfunction "1_1") (pintype "input"))
      (node (ref "U1") (pin "5") (pinfunction "IO2_5") (pintype "unspecified"))
    )
    (net (code "25") (name "Net-(U37-ISEN)") (class "Default")
      (node (ref "R13") (pin "2") (pinfunction "2_2") (pintype "input"))
      (node (ref "U37") (pin "7") (pinfunction "ISEN_7") (pintype "unspecified"))
    )
    (net (code "26") (name "Net-(U38-ISEN)") (class "Default")
      (node (ref "R14") (pin "2") (pinfunction "2_2") (pintype "input"))
      (node (ref "U38") (pin "7") (pinfunction "ISEN_7") (pintype "unspecified"))
    )
    (net (code "27") (name "RESET") (class "Default")
      (node (ref "C3") (pin "2") (pinfunction "2_2") (pintype "input"))
      (node (ref "C5") (pin "2") (pinfunction "2_2") (pintype "input"))
      (node (ref "R2") (pin "1") (pinfunction "1_1") (pintype "input"))
      (node (ref "U1") (pin "8") (pinfunction "EN_8") (pintype "unspecified"))
      (node (ref "U2") (pin "1") (pinfunction "1_1") (pintype "input"))
    )
    (net (code "28") (name "RX") (class "Default")
      (node (ref "H2") (pin "3") (pinfunction "3_3") (pintype "input"))
      (node (ref "U1") (pin "30") (pinfunction "RXD0_30") (pintype "unspecified"))
    )
    (net (code "29") (name "SERVO1") (class "Default")
      (node (ref "CN3") (pin "1") (pinfunction "1_1") (pintype "unspecified"))
      (node (ref "U1") (pin "18") (pinfunction "IO4_18") (pintype "unspecified"))
    )
    (net (code "30") (name "SERVO2") (class "Default")
      (node (ref "CN4") (pin "1") (pinfunction "1_1") (pintype "unspecified"))
      (node (ref "R3") (pin "2") (pinfunction "2_2") (pintype "input"))
      (node (ref "U1") (pin "22") (pinfunction "IO8_22") (pintype "unspecified"))
    )
    (net (code "31") (name "TX") (class "Default")
      (node (ref "H2") (pin "1") (pinfunction "1_1") (pintype "input"))
      (node (ref "U1") (pin "31") (pinfunction "TXD0_31") (pintype "unspecified"))
    )
    (net (code "32") (name "USB_VIN") (class "Default")
      (node (ref "D1") (pin "5") (pinfunction "VBUS_5") (pintype "input"))
      (node (ref "D8") (pin "2") (pinfunction "A_2") (pintype "input"))
      (node (ref "H2") (pin "4") (pinfunction "4_4") (pintype "input"))
      (node (ref "USB2") (pin "1") (pinfunction "VCC_1") (pintype "input"))
    )
    (net (code "33") (name "V_IN") (class "Default")
      (node (ref "C11") (pin "2") (pinfunction "2_2") (pintype "input"))
      (node (ref "C15") (pin "2") (pinfunction "2_2") (pintype "input"))
      (node (ref "C16") (pin "2") (pinfunction "2_2") (pintype "input"))
      (node (ref "C17") (pin "2") (pinfunction "2_2") (pintype "input"))
      (node (ref "C18") (pin "2") (pinfunction "2_2") (pintype "input"))
      (node (ref "D8") (pin "1") (pinfunction "K_1") (pintype "input"))
      (node (ref "LED3") (pin "2") (pinfunction "A_2") (pintype "input"))
      (node (ref "R12") (pin "2") (pinfunction "2_2") (pintype "unspecified"))
      (node (ref "U35") (pin "3") (pinfunction "INPUT_3") (pintype "unspecified"))
      (node (ref "U36") (pin "2") (pinfunction "2_2") (pintype "input"))
      (node (ref "U37") (pin "5") (pinfunction "VM_5") (pintype "unspecified"))
      (node (ref "U38") (pin "5") (pinfunction "VM_5") (pintype "unspecified"))
      (node (ref "U39") (pin "2") (pinfunction "2_2") (pintype "unspecified"))
      (node (ref "U40") (pin "2") (pinfunction "2_2") (pintype "unspecified"))
    )
    (net (code "34") (name "unconnected-(CN2-Pad3)") (class "Default")
      (node (ref "CN2") (pin "3") (pinfunction "3_3") (pintype "unspecified+no_connect"))
    )
    (net (code "35") (name "unconnected-(CN2-Pad4)") (class "Default")
      (node (ref "CN2") (pin "4") (pinfunction "4_4") (pintype "unspecified+no_connect"))
    )
    (net (code "36") (name "unconnected-(U1-NC-Pad4)") (class "Default")
      (node (ref "U1") (pin "4") (pinfunction "NC_4") (pintype "unspecified+no_connect"))
    )
    (net (code "37") (name "unconnected-(U1-NC-Pad7)") (class "Default")
      (node (ref "U1") (pin "7") (pinfunction "NC_7") (pintype "unspecified+no_connect"))
    )
    (net (code "38") (name "unconnected-(U1-NC-Pad9)") (class "Default")
      (node (ref "U1") (pin "9") (pinfunction "NC_9") (pintype "unspecified+no_connect"))
    )
    (net (code "39") (name "unconnected-(U1-NC-Pad10)") (class "Default")
      (node (ref "U1") (pin "10") (pinfunction "NC_10") (pintype "unspecified+no_connect"))
    )
    (net (code "40") (name "unconnected-(U1-NC-Pad15)") (class "Default")
      (node (ref "U1") (pin "15") (pinfunction "NC_15") (pintype "unspecified+no_connect"))
    )
    (net (code "41") (name "unconnected-(U1-NC-Pad17)") (class "Default")
      (node (ref "U1") (pin "17") (pinfunction "NC_17") (pintype "unspecified+no_connect"))
    )
    (net (code "42") (name "unconnected-(U1-NC-Pad24)") (class "Default")
      (node (ref "U1") (pin "24") (pinfunction "NC_24") (pintype "unspecified+no_connect"))
    )
    (net (code "43") (name "unconnected-(U1-NC-Pad25)") (class "Default")
      (node (ref "U1") (pin "25") (pinfunction "NC_25") (pintype "unspecified+no_connect"))
    )
    (net (code "44") (name "unconnected-(U1-NC-Pad28)") (class "Default")
      (node (ref "U1") (pin "28") (pinfunction "NC_28") (pintype "unspecified+no_connect"))
    )
    (net (code "45") (name "unconnected-(U1-NC-Pad29)") (class "Default")
      (node (ref "U1") (pin "29") (pinfunction "NC_29") (pintype "unspecified+no_connect"))
    )
    (net (code "46") (name "unconnected-(U1-NC-Pad32)") (class "Default")
      (node (ref "U1") (pin "32") (pinfunction "NC_32") (pintype "unspecified+no_connect"))
    )
    (net (code "47") (name "unconnected-(U1-NC-Pad33)") (class "Default")
      (node (ref "U1") (pin "33") (pinfunction "NC_33") (pintype "unspecified+no_connect"))
    )
    (net (code "48") (name "unconnected-(U1-NC-Pad34)") (class "Default")
      (node (ref "U1") (pin "34") (pinfunction "NC_34") (pintype "unspecified+no_connect"))
    )
    (net (code "49") (name "unconnected-(U1-NC-Pad35)") (class "Default")
      (node (ref "U1") (pin "35") (pinfunction "NC_35") (pintype "unspecified+no_connect"))
    )
    (net (code "50") (name "unconnected-(U39-Pad3)") (class "Default")
      (node (ref "U39") (pin "3") (pinfunction "3_3") (pintype "unspecified+no_connect"))
    )
    (net (code "51") (name "unconnected-(U39-Pad4)") (class "Default")
      (node (ref "U39") (pin "4") (pinfunction "4_4") (pintype "unspecified+no_connect"))
    )
    (net (code "52") (name "unconnected-(U40-Pad3)") (class "Default")
      (node (ref "U40") (pin "3") (pinfunction "3_3") (pintype "unspecified+no_connect"))
    )
    (net (code "53") (name "unconnected-(U40-Pad4)") (class "Default")
      (node (ref "U40") (pin "4") (pinfunction "4_4") (pintype "unspecified+no_connect"))
    )
    (net (code "54") (name "unconnected-(USB2-EH-Pad6)") (class "Default")
      (node (ref "USB2") (pin "6") (pinfunction "EH_6") (pintype "unspecified+no_connect"))
    )
  )
)
